# usbcpd.net
KiCad netlist of a schematic drawn in EAGLE
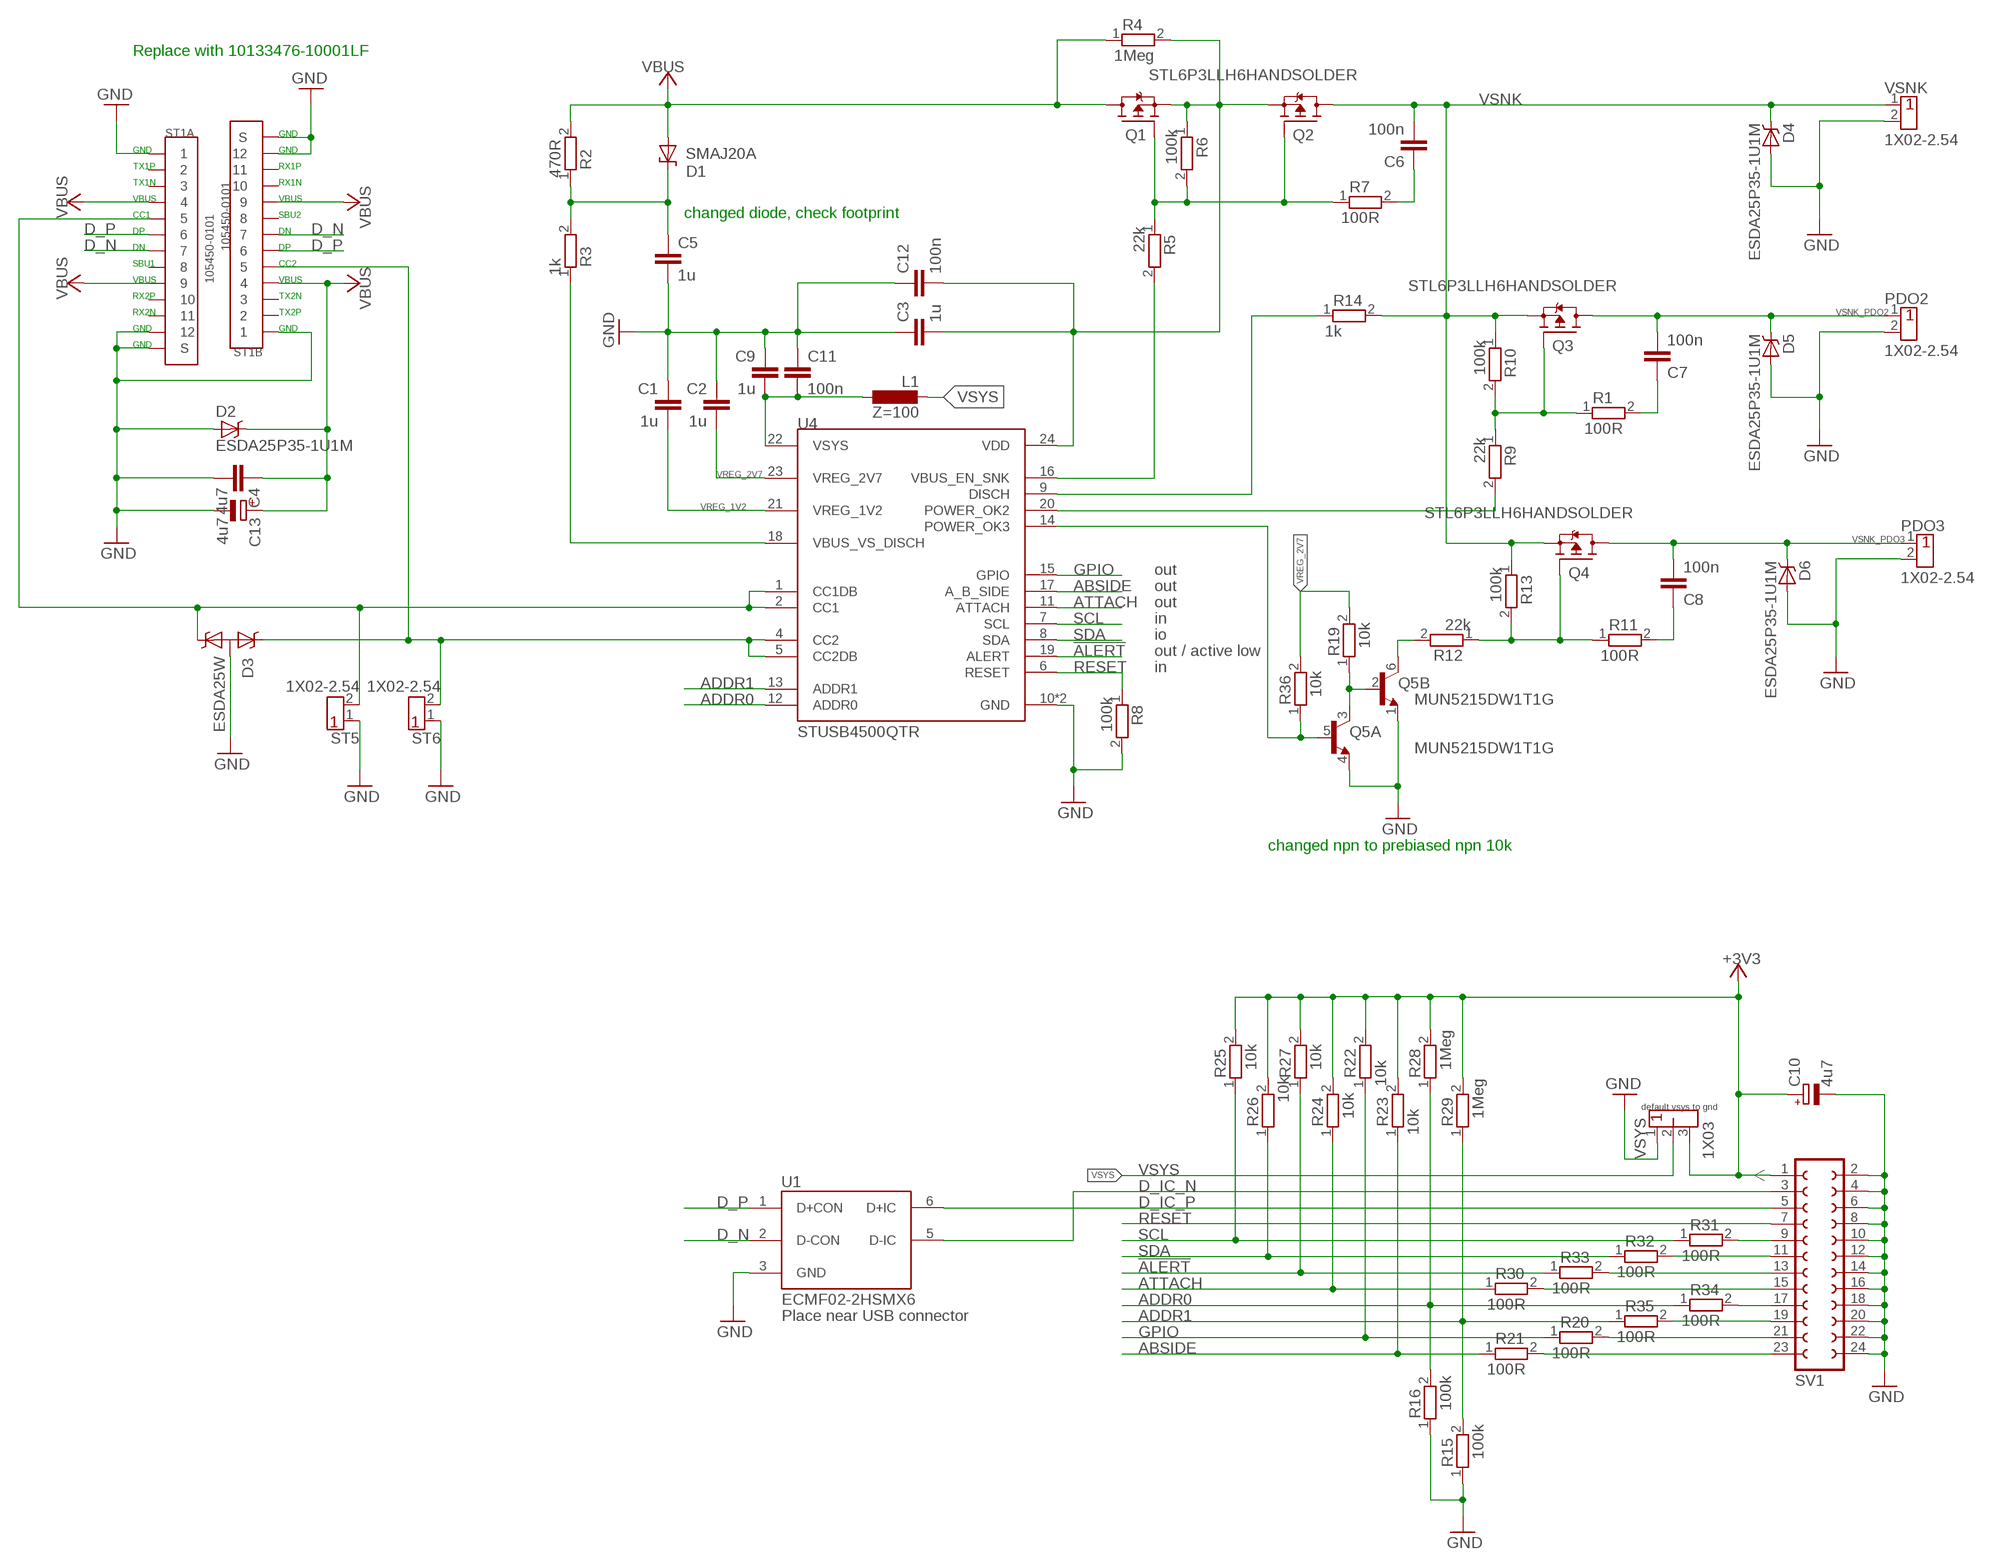
[diagram p0: schematic, sheet 1]

(export (version "E")
  (design (tool "Eeschema 10.0.6"))
  (components
    (comp (ref "C1")
      (value "1u")
      (footprint "eagle-import:0805")
      (libsource (lib "eagle-import") (part "C-EU0805"))
    )
    (comp (ref "C2")
      (value "1u")
      (footprint "eagle-import:0805")
      (libsource (lib "eagle-import") (part "C-EU0805"))
    )
    (comp (ref "C3")
      (value "1u")
      (footprint "eagle-import:0805")
      (libsource (lib "eagle-import") (part "C-EU0805"))
    )
    (comp (ref "C4")
      (value "4u7")
      (footprint "eagle-import:0805")
      (libsource (lib "eagle-import") (part "C-EU0805"))
    )
    (comp (ref "C5")
      (value "1u")
      (footprint "eagle-import:0805")
      (libsource (lib "eagle-import") (part "C-EU0805"))
    )
    (comp (ref "C6")
      (value "100n")
      (footprint "eagle-import:0805")
      (libsource (lib "eagle-import") (part "C-EU0805"))
    )
    (comp (ref "C7")
      (value "100n")
      (footprint "eagle-import:0805")
      (libsource (lib "eagle-import") (part "C-EU0805"))
    )
    (comp (ref "C8")
      (value "100n")
      (footprint "eagle-import:0805")
      (libsource (lib "eagle-import") (part "C-EU0805"))
    )
    (comp (ref "C9")
      (value "1u")
      (footprint "eagle-import:0805")
      (libsource (lib "eagle-import") (part "C-EU0805"))
    )
    (comp (ref "C10")
      (value "4u7")
      (footprint "eagle-import:E2-5")
      (libsource (lib "eagle-import") (part "CPOL-EUE2-5"))
    )
    (comp (ref "C11")
      (value "100n")
      (footprint "eagle-import:0805")
      (libsource (lib "eagle-import") (part "C-EU0805"))
    )
    (comp (ref "C12")
      (value "100n")
      (footprint "eagle-import:0805")
      (libsource (lib "eagle-import") (part "C-EU0805"))
    )
    (comp (ref "C13")
      (value "4u7")
      (footprint "eagle-import:E2-5")
      (libsource (lib "eagle-import") (part "CPOL-EUE2-5"))
    )
    (comp (ref "D1")
      (value "SMAJ20A")
      (footprint "eagle-import:SMBJ")
      (fields
        (field (name "MF") "STMICROELECTRONICS")
        (field (name "MPN") "SMBJ28A-TR")
        (field (name "MF_1") "Bourns")
        (field (name "MPN_1") "SMAJ20A")
      )
      (libsource (lib "eagle-import") (part "SMBJ28A"))
    )
    (comp (ref "D2")
      (value "ESDA25P35-1U1M")
      (footprint "eagle-import:QFN1610")
      (fields (field (name "MF") "ST MICROELECTRONICS"))
      (libsource (lib "eagle-import") (part "ESDA25P35-1U1M"))
    )
    (comp (ref "D3")
      (value "ESDA25W")
      (footprint "eagle-import:SOT323-3")
      (fields (field (name "MF") "ST MICROELECTRONICS"))
      (libsource (lib "eagle-import") (part "ESDA25W"))
    )
    (comp (ref "D4")
      (value "ESDA25P35-1U1M")
      (footprint "eagle-import:QFN1610")
      (fields (field (name "MF") "ST MICROELECTRONICS"))
      (libsource (lib "eagle-import") (part "ESDA25P35-1U1M"))
    )
    (comp (ref "D5")
      (value "ESDA25P35-1U1M")
      (footprint "eagle-import:QFN1610")
      (fields (field (name "MF") "ST MICROELECTRONICS"))
      (libsource (lib "eagle-import") (part "ESDA25P35-1U1M"))
    )
    (comp (ref "D6")
      (value "ESDA25P35-1U1M")
      (footprint "eagle-import:QFN1610")
      (fields (field (name "MF") "ST MICROELECTRONICS"))
      (libsource (lib "eagle-import") (part "ESDA25P35-1U1M"))
    )
    (comp (ref "L1")
      (value "Z=100")
      (footprint "eagle-import:0805")
      (fields (field (name "MF") "TDK") (field (name "MPN") "MPZ2012S101AT000"))
      (libsource (lib "eagle-import") (part "L-EU0805"))
    )
    (comp (ref "PDO2")
      (value "1X02-2.54")
      (footprint "eagle-import:1X02-2.54")
      (libsource (lib "eagle-import") (part "1X02-2.54"))
    )
    (comp (ref "PDO3")
      (value "1X02-2.54")
      (footprint "eagle-import:1X02-2.54")
      (libsource (lib "eagle-import") (part "1X02-2.54"))
    )
    (comp (ref "Q1")
      (value "STL6P3LLH6HANDSOLDER")
      (footprint "eagle-import:POWERFLAT-TYPEC-HANDSOLDER")
      (fields (field (name "MF") "ST MICROELECTRONICS") (field (name "MPN") "STL6P3LLH6"))
      (libsource (lib "eagle-import") (part "STL6P3LLH6HANDSOLDER"))
    )
    (comp (ref "Q2")
      (value "STL6P3LLH6HANDSOLDER")
      (footprint "eagle-import:POWERFLAT-TYPEC-HANDSOLDER")
      (fields (field (name "MF") "ST MICROELECTRONICS") (field (name "MPN") "STL6P3LLH6"))
      (libsource (lib "eagle-import") (part "STL6P3LLH6HANDSOLDER"))
    )
    (comp (ref "Q3")
      (value "STL6P3LLH6HANDSOLDER")
      (footprint "eagle-import:POWERFLAT-TYPEC-HANDSOLDER")
      (fields (field (name "MF") "ST MICROELECTRONICS") (field (name "MPN") "STL6P3LLH6"))
      (libsource (lib "eagle-import") (part "STL6P3LLH6HANDSOLDER"))
    )
    (comp (ref "Q4")
      (value "STL6P3LLH6HANDSOLDER")
      (footprint "eagle-import:POWERFLAT-TYPEC-HANDSOLDER")
      (fields (field (name "MF") "ST MICROELECTRONICS") (field (name "MPN") "STL6P3LLH6"))
      (libsource (lib "eagle-import") (part "STL6P3LLH6HANDSOLDER"))
    )
    (comp (ref "Q5")
      (value "MUN5215DW1T1G")
      (footprint "eagle-import:SOT363")
      (fields
        (field (name "MF") "ON SEMICONDUCTOR")
        (field (name "MPN") "BC847CDW1T1G")
        (field (name "MPN_1") "MUN5215DW1T1G")
        (field (name "OC_MOUSER") "863-MUN5215DW1T1G")
      )
      (libsource (lib "eagle-import") (part "BC847CDW1"))
    )
    (comp (ref "R1")
      (value "100R")
      (footprint "eagle-import:0805")
      (libsource (lib "eagle-import") (part "R-EU0805"))
    )
    (comp (ref "R2")
      (value "470R")
      (footprint "eagle-import:0805")
      (libsource (lib "eagle-import") (part "R-EU0805"))
    )
    (comp (ref "R3")
      (value "1k")
      (footprint "eagle-import:0805")
      (libsource (lib "eagle-import") (part "R-EU0805"))
    )
    (comp (ref "R4")
      (value "1Meg")
      (footprint "eagle-import:0805")
      (libsource (lib "eagle-import") (part "R-EU0805"))
    )
    (comp (ref "R5")
      (value "22k")
      (footprint "eagle-import:0805")
      (libsource (lib "eagle-import") (part "R-EU0805"))
    )
    (comp (ref "R6")
      (value "100k")
      (footprint "eagle-import:0805")
      (libsource (lib "eagle-import") (part "R-EU0805"))
    )
    (comp (ref "R7")
      (value "100R")
      (footprint "eagle-import:0805")
      (libsource (lib "eagle-import") (part "R-EU0805"))
    )
    (comp (ref "R8")
      (value "100k")
      (footprint "eagle-import:0805")
      (libsource (lib "eagle-import") (part "R-EU0805"))
    )
    (comp (ref "R9")
      (value "22k")
      (footprint "eagle-import:0805")
      (libsource (lib "eagle-import") (part "R-EU0805"))
    )
    (comp (ref "R10")
      (value "100k")
      (footprint "eagle-import:0805")
      (libsource (lib "eagle-import") (part "R-EU0805"))
    )
    (comp (ref "R11")
      (value "100R")
      (footprint "eagle-import:0805")
      (libsource (lib "eagle-import") (part "R-EU0805"))
    )
    (comp (ref "R12")
      (value "22k")
      (footprint "eagle-import:0805")
      (libsource (lib "eagle-import") (part "R-EU0805"))
    )
    (comp (ref "R13")
      (value "100k")
      (footprint "eagle-import:0805")
      (libsource (lib "eagle-import") (part "R-EU0805"))
    )
    (comp (ref "R14")
      (value "1k")
      (footprint "eagle-import:0805")
      (libsource (lib "eagle-import") (part "R-EU0805"))
    )
    (comp (ref "R15")
      (value "100k")
      (footprint "eagle-import:0805")
      (libsource (lib "eagle-import") (part "R-EU0805"))
    )
    (comp (ref "R16")
      (value "100k")
      (footprint "eagle-import:0805")
      (libsource (lib "eagle-import") (part "R-EU0805"))
    )
    (comp (ref "R19")
      (value "10k")
      (footprint "eagle-import:0805")
      (libsource (lib "eagle-import") (part "R-EU0805"))
    )
    (comp (ref "R20")
      (value "100R")
      (footprint "eagle-import:0805")
      (libsource (lib "eagle-import") (part "R-EU0805"))
    )
    (comp (ref "R21")
      (value "100R")
      (footprint "eagle-import:0805")
      (libsource (lib "eagle-import") (part "R-EU0805"))
    )
    (comp (ref "R22")
      (value "10k")
      (footprint "eagle-import:0805")
      (libsource (lib "eagle-import") (part "R-EU0805"))
    )
    (comp (ref "R23")
      (value "10k")
      (footprint "eagle-import:0805")
      (libsource (lib "eagle-import") (part "R-EU0805"))
    )
    (comp (ref "R24")
      (value "10k")
      (footprint "eagle-import:0805")
      (libsource (lib "eagle-import") (part "R-EU0805"))
    )
    (comp (ref "R25")
      (value "10k")
      (footprint "eagle-import:0805")
      (libsource (lib "eagle-import") (part "R-EU0805"))
    )
    (comp (ref "R26")
      (value "10k")
      (footprint "eagle-import:0805")
      (libsource (lib "eagle-import") (part "R-EU0805"))
    )
    (comp (ref "R27")
      (value "10k")
      (footprint "eagle-import:0805")
      (libsource (lib "eagle-import") (part "R-EU0805"))
    )
    (comp (ref "R28")
      (value "1Meg")
      (footprint "eagle-import:0805")
      (libsource (lib "eagle-import") (part "R-EU0805"))
    )
    (comp (ref "R29")
      (value "1Meg")
      (footprint "eagle-import:0805")
      (libsource (lib "eagle-import") (part "R-EU0805"))
    )
    (comp (ref "R30")
      (value "100R")
      (footprint "eagle-import:0805")
      (libsource (lib "eagle-import") (part "R-EU0805"))
    )
    (comp (ref "R31")
      (value "100R")
      (footprint "eagle-import:0805")
      (libsource (lib "eagle-import") (part "R-EU0805"))
    )
    (comp (ref "R32")
      (value "100R")
      (footprint "eagle-import:0805")
      (libsource (lib "eagle-import") (part "R-EU0805"))
    )
    (comp (ref "R33")
      (value "100R")
      (footprint "eagle-import:0805")
      (libsource (lib "eagle-import") (part "R-EU0805"))
    )
    (comp (ref "R34")
      (value "100R")
      (footprint "eagle-import:0805")
      (libsource (lib "eagle-import") (part "R-EU0805"))
    )
    (comp (ref "R35")
      (value "100R")
      (footprint "eagle-import:0805")
      (libsource (lib "eagle-import") (part "R-EU0805"))
    )
    (comp (ref "R36")
      (value "10k")
      (footprint "eagle-import:0805")
      (libsource (lib "eagle-import") (part "R-EU0805"))
    )
    (comp (ref "ST1")
      (value "105450-0101")
      (footprint "eagle-import:105450-0101")
      (fields (field (name "MF") "Molex"))
      (libsource (lib "eagle-import") (part "105450-0101"))
    )
    (comp (ref "ST5")
      (value "1X02-2.54")
      (footprint "eagle-import:1X02-2.54")
      (libsource (lib "eagle-import") (part "1X02-2.54"))
    )
    (comp (ref "ST6")
      (value "1X02-2.54")
      (footprint "eagle-import:1X02-2.54")
      (libsource (lib "eagle-import") (part "1X02-2.54"))
    )
    (comp (ref "SV1")
      (value "FE12-2")
      (footprint "eagle-import:FE12-2")
      (libsource (lib "eagle-import") (part "FE12-2"))
    )
    (comp (ref "U1")
      (value "ECMF02-2HSMX6")
      (footprint "eagle-import:UQFN6")
      (fields (field (name "MF") "STMicroelectronics ") (field (name "MPN") "ECMF02-2HSMX6 "))
      (libsource (lib "eagle-import") (part "ECMF02-2HSMX6"))
    )
    (comp (ref "U4")
      (value "STUSB4500QTR")
      (footprint "eagle-import:QFN24EP")
      (fields (field (name "MF") "ST MICROELECTRONICS") (field (name "SPICEPREFIX") "X"))
      (libsource (lib "eagle-import") (part "STUSB4500QTR"))
    )
    (comp (ref "VSNK")
      (value "1X02-2.54")
      (footprint "eagle-import:1X02-2.54")
      (libsource (lib "eagle-import") (part "1X02-2.54"))
    )
    (comp (ref "VSYS")
      (value "1X03")
      (footprint "eagle-import:1X03-2.54")
      (fields (field (name "MF") "MULTICOMP") (field (name "MPN") "2211S-03G"))
      (libsource (lib "eagle-import") (part "1X03"))
    )
  )
  (nets
    (net (code "1") (name "+3V3") (class "Default")
      (node (ref "C10") (pin "+") (pinfunction "+_+") (pintype "passive"))
      (node (ref "R22") (pin "2") (pinfunction "2_2") (pintype "passive"))
      (node (ref "R23") (pin "2") (pinfunction "2_2") (pintype "passive"))
      (node (ref "R24") (pin "2") (pinfunction "2_2") (pintype "passive"))
      (node (ref "R25") (pin "2") (pinfunction "2_2") (pintype "passive"))
      (node (ref "R26") (pin "2") (pinfunction "2_2") (pintype "passive"))
      (node (ref "R27") (pin "2") (pinfunction "2_2") (pintype "passive"))
      (node (ref "R28") (pin "2") (pinfunction "2_2") (pintype "passive"))
      (node (ref "R29") (pin "2") (pinfunction "2_2") (pintype "passive"))
      (node (ref "SV1") (pin "1") (pinfunction "1_1") (pintype "passive"))
      (node (ref "VSYS") (pin "3") (pinfunction "3_3") (pintype "passive"))
    )
    (net (code "2") (name "/ABSIDE") (class "Default")
      (node (ref "R21") (pin "1") (pinfunction "1_1") (pintype "passive"))
      (node (ref "R23") (pin "1") (pinfunction "1_1") (pintype "passive"))
      (node (ref "U4") (pin "17") (pinfunction "A_B_SIDE_17") (pintype "open_collector"))
    )
    (net (code "3") (name "/ADDR0") (class "Default")
      (node (ref "R16") (pin "2") (pinfunction "2_2") (pintype "passive"))
      (node (ref "R28") (pin "1") (pinfunction "1_1") (pintype "passive"))
      (node (ref "R34") (pin "1") (pinfunction "1_1") (pintype "passive"))
      (node (ref "U4") (pin "12") (pinfunction "ADDR0_12") (pintype "input"))
    )
    (net (code "4") (name "/ADDR1") (class "Default")
      (node (ref "R15") (pin "2") (pinfunction "2_2") (pintype "passive"))
      (node (ref "R29") (pin "1") (pinfunction "1_1") (pintype "passive"))
      (node (ref "R35") (pin "1") (pinfunction "1_1") (pintype "passive"))
      (node (ref "U4") (pin "13") (pinfunction "ADDR1_13") (pintype "input"))
    )
    (net (code "5") (name "/ATTACH") (class "Default")
      (node (ref "R24") (pin "1") (pinfunction "1_1") (pintype "passive"))
      (node (ref "R30") (pin "1") (pinfunction "1_1") (pintype "passive"))
      (node (ref "U4") (pin "11") (pinfunction "ATTACH_11") (pintype "open_collector"))
    )
    (net (code "6") (name "/D_IC_N") (class "Default")
      (node (ref "SV1") (pin "3") (pinfunction "3_3") (pintype "passive"))
      (node (ref "U1") (pin "5") (pinfunction "D-IC_5") (pintype "passive"))
    )
    (net (code "7") (name "/D_IC_P") (class "Default")
      (node (ref "SV1") (pin "5") (pinfunction "5_5") (pintype "passive"))
      (node (ref "U1") (pin "6") (pinfunction "D+IC_6") (pintype "passive"))
    )
    (net (code "8") (name "/D_N") (class "Default")
      (node (ref "ST1") (pin "A7") (pinfunction "7_A7") (pintype "passive"))
      (node (ref "ST1") (pin "B7") (pinfunction "7_B7") (pintype "passive"))
      (node (ref "U1") (pin "2") (pinfunction "D-CON_2") (pintype "passive"))
    )
    (net (code "9") (name "/D_P") (class "Default")
      (node (ref "ST1") (pin "A6") (pinfunction "6_A6") (pintype "passive"))
      (node (ref "ST1") (pin "B6") (pinfunction "6_B6") (pintype "passive"))
      (node (ref "U1") (pin "1") (pinfunction "D+CON_1") (pintype "passive"))
    )
    (net (code "10") (name "/GPIO") (class "Default")
      (node (ref "R20") (pin "1") (pinfunction "1_1") (pintype "passive"))
      (node (ref "R22") (pin "1") (pinfunction "1_1") (pintype "passive"))
      (node (ref "U4") (pin "15") (pinfunction "GPIO_15") (pintype "open_collector"))
    )
    (net (code "11") (name "/RESET") (class "Default")
      (node (ref "R8") (pin "1") (pinfunction "1_1") (pintype "passive"))
      (node (ref "SV1") (pin "7") (pinfunction "7_7") (pintype "passive"))
      (node (ref "U4") (pin "6") (pinfunction "RESET_6") (pintype "input"))
    )
    (net (code "12") (name "/SCL") (class "Default")
      (node (ref "R25") (pin "1") (pinfunction "1_1") (pintype "passive"))
      (node (ref "R31") (pin "1") (pinfunction "1_1") (pintype "passive"))
      (node (ref "U4") (pin "7") (pinfunction "SCL_7") (pintype "input"))
    )
    (net (code "13") (name "/SDA") (class "Default")
      (node (ref "R26") (pin "1") (pinfunction "1_1") (pintype "passive"))
      (node (ref "R32") (pin "1") (pinfunction "1_1") (pintype "passive"))
      (node (ref "U4") (pin "8") (pinfunction "SDA_8") (pintype "bidirectional"))
    )
    (net (code "14") (name "/VREG_1V2") (class "Default")
      (node (ref "C1") (pin "2") (pinfunction "2_2") (pintype "passive"))
      (node (ref "U4") (pin "21") (pinfunction "VREG_1V2_21") (pintype "passive"))
    )
    (net (code "15") (name "/VSNK") (class "Default")
      (node (ref "C6") (pin "2") (pinfunction "2_2") (pintype "passive"))
      (node (ref "D4") (pin "1") (pinfunction "C_1") (pintype "passive"))
      (node (ref "Q2") (pin "5") (pinfunction "D_5") (pintype "passive"))
      (node (ref "Q3") (pin "1") (pinfunction "S_1") (pintype "passive"))
      (node (ref "Q3") (pin "2") (pinfunction "S_2") (pintype "passive"))
      (node (ref "Q3") (pin "3") (pinfunction "S_3") (pintype "passive"))
      (node (ref "Q4") (pin "1") (pinfunction "S_1") (pintype "passive"))
      (node (ref "Q4") (pin "2") (pinfunction "S_2") (pintype "passive"))
      (node (ref "Q4") (pin "3") (pinfunction "S_3") (pintype "passive"))
      (node (ref "R10") (pin "1") (pinfunction "1_1") (pintype "passive"))
      (node (ref "R13") (pin "1") (pinfunction "1_1") (pintype "passive"))
      (node (ref "R14") (pin "2") (pinfunction "2_2") (pintype "passive"))
      (node (ref "VSNK") (pin "1") (pinfunction "1_1") (pintype "passive"))
    )
    (net (code "16") (name "/VSNK_PDO2") (class "Default")
      (node (ref "C7") (pin "2") (pinfunction "2_2") (pintype "passive"))
      (node (ref "D5") (pin "1") (pinfunction "C_1") (pintype "passive"))
      (node (ref "PDO2") (pin "1") (pinfunction "1_1") (pintype "passive"))
      (node (ref "Q3") (pin "5") (pinfunction "D_5") (pintype "passive"))
    )
    (net (code "17") (name "/VSNK_PDO3") (class "Default")
      (node (ref "C8") (pin "2") (pinfunction "2_2") (pintype "passive"))
      (node (ref "D6") (pin "1") (pinfunction "C_1") (pintype "passive"))
      (node (ref "PDO3") (pin "1") (pinfunction "1_1") (pintype "passive"))
      (node (ref "Q4") (pin "5") (pinfunction "D_5") (pintype "passive"))
    )
    (net (code "18") (name "/~{ALERT}") (class "Default")
      (node (ref "R27") (pin "1") (pinfunction "1_1") (pintype "passive"))
      (node (ref "R33") (pin "1") (pinfunction "1_1") (pintype "passive"))
      (node (ref "U4") (pin "19") (pinfunction "ALERT_19") (pintype "open_collector"))
    )
    (net (code "19") (name "GND") (class "Default")
      (node (ref "C1") (pin "1") (pinfunction "1_1") (pintype "passive"))
      (node (ref "C10") (pin "-") (pinfunction "-_-") (pintype "passive"))
      (node (ref "C11") (pin "1") (pinfunction "1_1") (pintype "passive"))
      (node (ref "C12") (pin "1") (pinfunction "1_1") (pintype "passive"))
      (node (ref "C13") (pin "-") (pinfunction "-_-") (pintype "passive"))
      (node (ref "C2") (pin "1") (pinfunction "1_1") (pintype "passive"))
      (node (ref "C3") (pin "1") (pinfunction "1_1") (pintype "passive"))
      (node (ref "C4") (pin "2") (pinfunction "2_2") (pintype "passive"))
      (node (ref "C5") (pin "2") (pinfunction "2_2") (pintype "passive"))
      (node (ref "C9") (pin "1") (pinfunction "1_1") (pintype "passive"))
      (node (ref "D2") (pin "2") (pinfunction "A_2") (pintype "passive"))
      (node (ref "D3") (pin "3") (pinfunction "A_3") (pintype "passive"))
      (node (ref "D4") (pin "2") (pinfunction "A_2") (pintype "passive"))
      (node (ref "D5") (pin "2") (pinfunction "A_2") (pintype "passive"))
      (node (ref "D6") (pin "2") (pinfunction "A_2") (pintype "passive"))
      (node (ref "PDO2") (pin "2") (pinfunction "2_2") (pintype "passive"))
      (node (ref "PDO3") (pin "2") (pinfunction "2_2") (pintype "passive"))
      (node (ref "Q5") (pin "1") (pinfunction "E_1") (pintype "passive"))
      (node (ref "Q5") (pin "4") (pinfunction "E_4") (pintype "passive"))
      (node (ref "R15") (pin "1") (pinfunction "1_1") (pintype "passive"))
      (node (ref "R16") (pin "1") (pinfunction "1_1") (pintype "passive"))
      (node (ref "R8") (pin "2") (pinfunction "2_2") (pintype "passive"))
      (node (ref "ST1") (pin "A1") (pinfunction "1_A1") (pintype "passive"))
      (node (ref "ST1") (pin "A12") (pinfunction "12_A12") (pintype "passive"))
      (node (ref "ST1") (pin "B1") (pinfunction "1_B1") (pintype "passive"))
      (node (ref "ST1") (pin "B12") (pinfunction "12_B12") (pintype "passive"))
      (node (ref "ST1") (pin "G1") (pinfunction "S_G1") (pintype "passive"))
      (node (ref "ST1") (pin "G10") (pinfunction "S_G10") (pintype "passive"))
      (node (ref "ST1") (pin "G11") (pinfunction "S_G11") (pintype "passive"))
      (node (ref "ST1") (pin "G12") (pinfunction "S_G12") (pintype "passive"))
      (node (ref "ST1") (pin "G13") (pinfunction "S_G13") (pintype "passive"))
      (node (ref "ST1") (pin "G14") (pinfunction "S_G14") (pintype "passive"))
      (node (ref "ST1") (pin "G15") (pinfunction "S_G15") (pintype "passive"))
      (node (ref "ST1") (pin "G16") (pinfunction "S_G16") (pintype "passive"))
      (node (ref "ST1") (pin "G17") (pinfunction "S_G17") (pintype "passive"))
      (node (ref "ST1") (pin "G18") (pinfunction "S_G18") (pintype "passive"))
      (node (ref "ST1") (pin "G19") (pinfunction "S_G19") (pintype "passive"))
      (node (ref "ST1") (pin "G2") (pinfunction "S_G2") (pintype "passive"))
      (node (ref "ST1") (pin "G20") (pinfunction "S_G20") (pintype "passive"))
      (node (ref "ST1") (pin "G21") (pinfunction "S_G21") (pintype "passive"))
      (node (ref "ST1") (pin "G22") (pinfunction "S_G22") (pintype "passive"))
      (node (ref "ST1") (pin "G23") (pinfunction "S_G23") (pintype "passive"))
      (node (ref "ST1") (pin "G24") (pinfunction "S_G24") (pintype "passive"))
      (node (ref "ST1") (pin "G25") (pinfunction "S_G25") (pintype "passive"))
      (node (ref "ST1") (pin "G26") (pinfunction "S_G26") (pintype "passive"))
      (node (ref "ST1") (pin "G27") (pinfunction "S_G27") (pintype "passive"))
      (node (ref "ST1") (pin "G28") (pinfunction "S_G28") (pintype "passive"))
      (node (ref "ST1") (pin "G29") (pinfunction "S_G29") (pintype "passive"))
      (node (ref "ST1") (pin "G3") (pinfunction "S_G3") (pintype "passive"))
      (node (ref "ST1") (pin "G30") (pinfunction "S_G30") (pintype "passive"))
      (node (ref "ST1") (pin "G31") (pinfunction "S_G31") (pintype "passive"))
      (node (ref "ST1") (pin "G32") (pinfunction "S_G32") (pintype "passive"))
      (node (ref "ST1") (pin "G33") (pinfunction "S_G33") (pintype "passive"))
      (node (ref "ST1") (pin "G4") (pinfunction "S_G4") (pintype "passive"))
      (node (ref "ST1") (pin "G5") (pinfunction "S_G5") (pintype "passive"))
      (node (ref "ST1") (pin "G6") (pinfunction "S_G6") (pintype "passive"))
      (node (ref "ST1") (pin "G7") (pinfunction "S_G7") (pintype "passive"))
      (node (ref "ST1") (pin "G8") (pinfunction "S_G8") (pintype "passive"))
      (node (ref "ST1") (pin "G9") (pinfunction "S_G9") (pintype "passive"))
      (node (ref "ST5") (pin "1") (pinfunction "1_1") (pintype "passive"))
      (node (ref "ST6") (pin "1") (pinfunction "1_1") (pintype "passive"))
      (node (ref "SV1") (pin "10") (pinfunction "10_10") (pintype "passive"))
      (node (ref "SV1") (pin "12") (pinfunction "12_12") (pintype "passive"))
      (node (ref "SV1") (pin "14") (pinfunction "14_14") (pintype "passive"))
      (node (ref "SV1") (pin "16") (pinfunction "16_16") (pintype "passive"))
      (node (ref "SV1") (pin "18") (pinfunction "18_18") (pintype "passive"))
      (node (ref "SV1") (pin "2") (pinfunction "2_2") (pintype "passive"))
      (node (ref "SV1") (pin "20") (pinfunction "20_20") (pintype "passive"))
      (node (ref "SV1") (pin "22") (pinfunction "22_22") (pintype "passive"))
      (node (ref "SV1") (pin "24") (pinfunction "24_24") (pintype "passive"))
      (node (ref "SV1") (pin "4") (pinfunction "4_4") (pintype "passive"))
      (node (ref "SV1") (pin "6") (pinfunction "6_6") (pintype "passive"))
      (node (ref "SV1") (pin "8") (pinfunction "8_8") (pintype "passive"))
      (node (ref "U1") (pin "3") (pinfunction "GND_3") (pintype "power_in"))
      (node (ref "U4") (pin "10") (pinfunction "GND_10") (pintype "bidirectional"))
      (node (ref "U4") (pin "TP") (pinfunction "GND_TP") (pintype "bidirectional"))
      (node (ref "VSNK") (pin "2") (pinfunction "2_2") (pintype "passive"))
      (node (ref "VSYS") (pin "1") (pinfunction "1_1") (pintype "passive"))
    )
    (net (code "20") (name "Net-(C5-Pad1)") (class "Default")
      (node (ref "C5") (pin "1") (pinfunction "1_1") (pintype "passive"))
      (node (ref "D1") (pin "C") (pinfunction "C_C") (pintype "passive"))
      (node (ref "R2") (pin "1") (pinfunction "1_1") (pintype "passive"))
      (node (ref "R3") (pin "2") (pinfunction "2_2") (pintype "passive"))
    )
    (net (code "21") (name "Net-(C6-Pad1)") (class "Default")
      (node (ref "C6") (pin "1") (pinfunction "1_1") (pintype "passive"))
      (node (ref "R7") (pin "2") (pinfunction "2_2") (pintype "passive"))
    )
    (net (code "22") (name "Net-(C7-Pad1)") (class "Default")
      (node (ref "C7") (pin "1") (pinfunction "1_1") (pintype "passive"))
      (node (ref "R1") (pin "2") (pinfunction "2_2") (pintype "passive"))
    )
    (net (code "23") (name "Net-(C8-Pad1)") (class "Default")
      (node (ref "C8") (pin "1") (pinfunction "1_1") (pintype "passive"))
      (node (ref "R11") (pin "2") (pinfunction "2_2") (pintype "passive"))
    )
    (net (code "24") (name "Net-(D3-C1)") (class "Default")
      (node (ref "D3") (pin "1") (pinfunction "C1_1") (pintype "passive"))
      (node (ref "ST1") (pin "B5") (pinfunction "5_B5") (pintype "passive"))
      (node (ref "ST6") (pin "2") (pinfunction "2_2") (pintype "passive"))
      (node (ref "U4") (pin "4") (pinfunction "CC2_4") (pintype "passive"))
      (node (ref "U4") (pin "5") (pinfunction "CC2DB_5") (pintype "passive"))
    )
    (net (code "25") (name "Net-(D3-C2)") (class "Default")
      (node (ref "D3") (pin "2") (pinfunction "C2_2") (pintype "passive"))
      (node (ref "ST1") (pin "A5") (pinfunction "5_A5") (pintype "passive"))
      (node (ref "ST5") (pin "2") (pinfunction "2_2") (pintype "passive"))
      (node (ref "U4") (pin "1") (pinfunction "CC1DB_1") (pintype "passive"))
      (node (ref "U4") (pin "2") (pinfunction "CC1_2") (pintype "passive"))
    )
    (net (code "26") (name "Net-(Q1-G)") (class "Default")
      (node (ref "Q1") (pin "4") (pinfunction "G_4") (pintype "passive"))
      (node (ref "Q2") (pin "4") (pinfunction "G_4") (pintype "passive"))
      (node (ref "R5") (pin "1") (pinfunction "1_1") (pintype "passive"))
      (node (ref "R6") (pin "2") (pinfunction "2_2") (pintype "passive"))
      (node (ref "R7") (pin "1") (pinfunction "1_1") (pintype "passive"))
    )
    (net (code "27") (name "Net-(Q3-G)") (class "Default")
      (node (ref "Q3") (pin "4") (pinfunction "G_4") (pintype "passive"))
      (node (ref "R1") (pin "1") (pinfunction "1_1") (pintype "passive"))
      (node (ref "R10") (pin "2") (pinfunction "2_2") (pintype "passive"))
      (node (ref "R9") (pin "1") (pinfunction "1_1") (pintype "passive"))
    )
    (net (code "28") (name "Net-(Q4-G)") (class "Default")
      (node (ref "Q4") (pin "4") (pinfunction "G_4") (pintype "passive"))
      (node (ref "R11") (pin "1") (pinfunction "1_1") (pintype "passive"))
      (node (ref "R12") (pin "1") (pinfunction "1_1") (pintype "passive"))
      (node (ref "R13") (pin "2") (pinfunction "2_2") (pintype "passive"))
    )
    (net (code "29") (name "Net-(Q5A-B)") (class "Default")
      (node (ref "Q5") (pin "5") (pinfunction "B_5") (pintype "passive"))
      (node (ref "R36") (pin "1") (pinfunction "1_1") (pintype "passive"))
      (node (ref "U4") (pin "14") (pinfunction "POWER_OK3_14") (pintype "open_collector"))
    )
    (net (code "30") (name "Net-(Q5A-C)") (class "Default")
      (node (ref "Q5") (pin "2") (pinfunction "B_2") (pintype "passive"))
      (node (ref "Q5") (pin "3") (pinfunction "C_3") (pintype "passive"))
      (node (ref "R19") (pin "1") (pinfunction "1_1") (pintype "passive"))
    )
    (net (code "31") (name "Net-(Q5B-C)") (class "Default")
      (node (ref "Q5") (pin "6") (pinfunction "C_6") (pintype "passive"))
      (node (ref "R12") (pin "2") (pinfunction "2_2") (pintype "passive"))
    )
    (net (code "32") (name "Net-(R20-Pad2)") (class "Default")
      (node (ref "R20") (pin "2") (pinfunction "2_2") (pintype "passive"))
      (node (ref "SV1") (pin "21") (pinfunction "21_21") (pintype "passive"))
    )
    (net (code "33") (name "Net-(R21-Pad2)") (class "Default")
      (node (ref "R21") (pin "2") (pinfunction "2_2") (pintype "passive"))
      (node (ref "SV1") (pin "23") (pinfunction "23_23") (pintype "passive"))
    )
    (net (code "34") (name "Net-(R30-Pad2)") (class "Default")
      (node (ref "R30") (pin "2") (pinfunction "2_2") (pintype "passive"))
      (node (ref "SV1") (pin "15") (pinfunction "15_15") (pintype "passive"))
    )
    (net (code "35") (name "Net-(R31-Pad2)") (class "Default")
      (node (ref "R31") (pin "2") (pinfunction "2_2") (pintype "passive"))
      (node (ref "SV1") (pin "9") (pinfunction "9_9") (pintype "passive"))
    )
    (net (code "36") (name "Net-(R32-Pad2)") (class "Default")
      (node (ref "R32") (pin "2") (pinfunction "2_2") (pintype "passive"))
      (node (ref "SV1") (pin "11") (pinfunction "11_11") (pintype "passive"))
    )
    (net (code "37") (name "Net-(R33-Pad2)") (class "Default")
      (node (ref "R33") (pin "2") (pinfunction "2_2") (pintype "passive"))
      (node (ref "SV1") (pin "13") (pinfunction "13_13") (pintype "passive"))
    )
    (net (code "38") (name "Net-(R34-Pad2)") (class "Default")
      (node (ref "R34") (pin "2") (pinfunction "2_2") (pintype "passive"))
      (node (ref "SV1") (pin "17") (pinfunction "17_17") (pintype "passive"))
    )
    (net (code "39") (name "Net-(R35-Pad2)") (class "Default")
      (node (ref "R35") (pin "2") (pinfunction "2_2") (pintype "passive"))
      (node (ref "SV1") (pin "19") (pinfunction "19_19") (pintype "passive"))
    )
    (net (code "40") (name "Net-(U4-DISCH)") (class "Default")
      (node (ref "R14") (pin "1") (pinfunction "1_1") (pintype "passive"))
      (node (ref "U4") (pin "9") (pinfunction "DISCH_9") (pintype "passive"))
    )
    (net (code "41") (name "Net-(U4-POWER_OK2)") (class "Default")
      (node (ref "R9") (pin "2") (pinfunction "2_2") (pintype "passive"))
      (node (ref "U4") (pin "20") (pinfunction "POWER_OK2_20") (pintype "open_collector"))
    )
    (net (code "42") (name "Net-(U4-VBUS_EN_SNK)") (class "Default")
      (node (ref "R5") (pin "2") (pinfunction "2_2") (pintype "passive"))
      (node (ref "U4") (pin "16") (pinfunction "VBUS_EN_SNK_16") (pintype "open_collector"))
    )
    (net (code "43") (name "Net-(U4-VBUS_VS_DISCH)") (class "Default")
      (node (ref "R3") (pin "1") (pinfunction "1_1") (pintype "passive"))
      (node (ref "U4") (pin "18") (pinfunction "VBUS_VS_DISCH_18") (pintype "bidirectional"))
    )
    (net (code "44") (name "Net-(U4-VDD)") (class "Default")
      (node (ref "C12") (pin "2") (pinfunction "2_2") (pintype "passive"))
      (node (ref "C3") (pin "2") (pinfunction "2_2") (pintype "passive"))
      (node (ref "Q1") (pin "1") (pinfunction "S_1") (pintype "passive"))
      (node (ref "Q1") (pin "2") (pinfunction "S_2") (pintype "passive"))
      (node (ref "Q1") (pin "3") (pinfunction "S_3") (pintype "passive"))
      (node (ref "Q2") (pin "1") (pinfunction "S_1") (pintype "passive"))
      (node (ref "Q2") (pin "2") (pinfunction "S_2") (pintype "passive"))
      (node (ref "Q2") (pin "3") (pinfunction "S_3") (pintype "passive"))
      (node (ref "R4") (pin "2") (pinfunction "2_2") (pintype "passive"))
      (node (ref "R6") (pin "1") (pinfunction "1_1") (pintype "passive"))
      (node (ref "U4") (pin "24") (pinfunction "VDD_24") (pintype "power_in"))
    )
    (net (code "45") (name "Net-(U4-VSYS)") (class "Default")
      (node (ref "C11") (pin "2") (pinfunction "2_2") (pintype "passive"))
      (node (ref "C9") (pin "2") (pinfunction "2_2") (pintype "passive"))
      (node (ref "L1") (pin "1") (pinfunction "1_1") (pintype "passive"))
      (node (ref "U4") (pin "22") (pinfunction "VSYS_22") (pintype "power_in"))
    )
    (net (code "46") (name "VBUS") (class "Default")
      (node (ref "C13") (pin "+") (pinfunction "+_+") (pintype "passive"))
      (node (ref "C4") (pin "1") (pinfunction "1_1") (pintype "passive"))
      (node (ref "D1") (pin "A") (pinfunction "A_A") (pintype "passive"))
      (node (ref "D2") (pin "1") (pinfunction "C_1") (pintype "passive"))
      (node (ref "Q1") (pin "5") (pinfunction "D_5") (pintype "passive"))
      (node (ref "R2") (pin "2") (pinfunction "2_2") (pintype "passive"))
      (node (ref "R4") (pin "1") (pinfunction "1_1") (pintype "passive"))
      (node (ref "ST1") (pin "A4") (pinfunction "4_A4") (pintype "passive"))
      (node (ref "ST1") (pin "A9") (pinfunction "9_A9") (pintype "passive"))
      (node (ref "ST1") (pin "B4") (pinfunction "4_B4") (pintype "passive"))
      (node (ref "ST1") (pin "B9") (pinfunction "9_B9") (pintype "passive"))
    )
    (net (code "47") (name "VREG_2V7") (class "Default")
      (node (ref "C2") (pin "2") (pinfunction "2_2") (pintype "passive"))
      (node (ref "R19") (pin "2") (pinfunction "2_2") (pintype "passive"))
      (node (ref "R36") (pin "2") (pinfunction "2_2") (pintype "passive"))
      (node (ref "U4") (pin "23") (pinfunction "VREG_2V7_23") (pintype "passive"))
    )
    (net (code "48") (name "VSYS") (class "Default")
      (node (ref "L1") (pin "2") (pinfunction "2_2") (pintype "passive"))
      (node (ref "VSYS") (pin "2") (pinfunction "2_2") (pintype "passive"))
    )
    (net (code "49") (name "unconnected-(ST1A-2-PadA2)") (class "Default")
      (node (ref "ST1") (pin "A2") (pinfunction "2_A2") (pintype "passive"))
    )
    (net (code "50") (name "unconnected-(ST1A-3-PadA3)") (class "Default")
      (node (ref "ST1") (pin "A3") (pinfunction "3_A3") (pintype "passive"))
    )
    (net (code "51") (name "unconnected-(ST1A-8-PadA8)") (class "Default")
      (node (ref "ST1") (pin "A8") (pinfunction "8_A8") (pintype "passive"))
    )
    (net (code "52") (name "unconnected-(ST1A-10-PadA10)") (class "Default")
      (node (ref "ST1") (pin "A10") (pinfunction "10_A10") (pintype "passive"))
    )
    (net (code "53") (name "unconnected-(ST1A-11-PadA11)") (class "Default")
      (node (ref "ST1") (pin "A11") (pinfunction "11_A11") (pintype "passive"))
    )
    (net (code "54") (name "unconnected-(ST1B-2-PadB2)") (class "Default")
      (node (ref "ST1") (pin "B2") (pinfunction "2_B2") (pintype "passive"))
    )
    (net (code "55") (name "unconnected-(ST1B-3-PadB3)") (class "Default")
      (node (ref "ST1") (pin "B3") (pinfunction "3_B3") (pintype "passive"))
    )
    (net (code "56") (name "unconnected-(ST1B-8-PadB8)") (class "Default")
      (node (ref "ST1") (pin "B8") (pinfunction "8_B8") (pintype "passive"))
    )
    (net (code "57") (name "unconnected-(ST1B-10-PadB10)") (class "Default")
      (node (ref "ST1") (pin "B10") (pinfunction "10_B10") (pintype "passive"))
    )
    (net (code "58") (name "unconnected-(ST1B-11-PadB11)") (class "Default")
      (node (ref "ST1") (pin "B11") (pinfunction "11_B11") (pintype "passive"))
    )
  )
)
